# W706.net
KiCad netlist of a schematic drawn in EAGLE
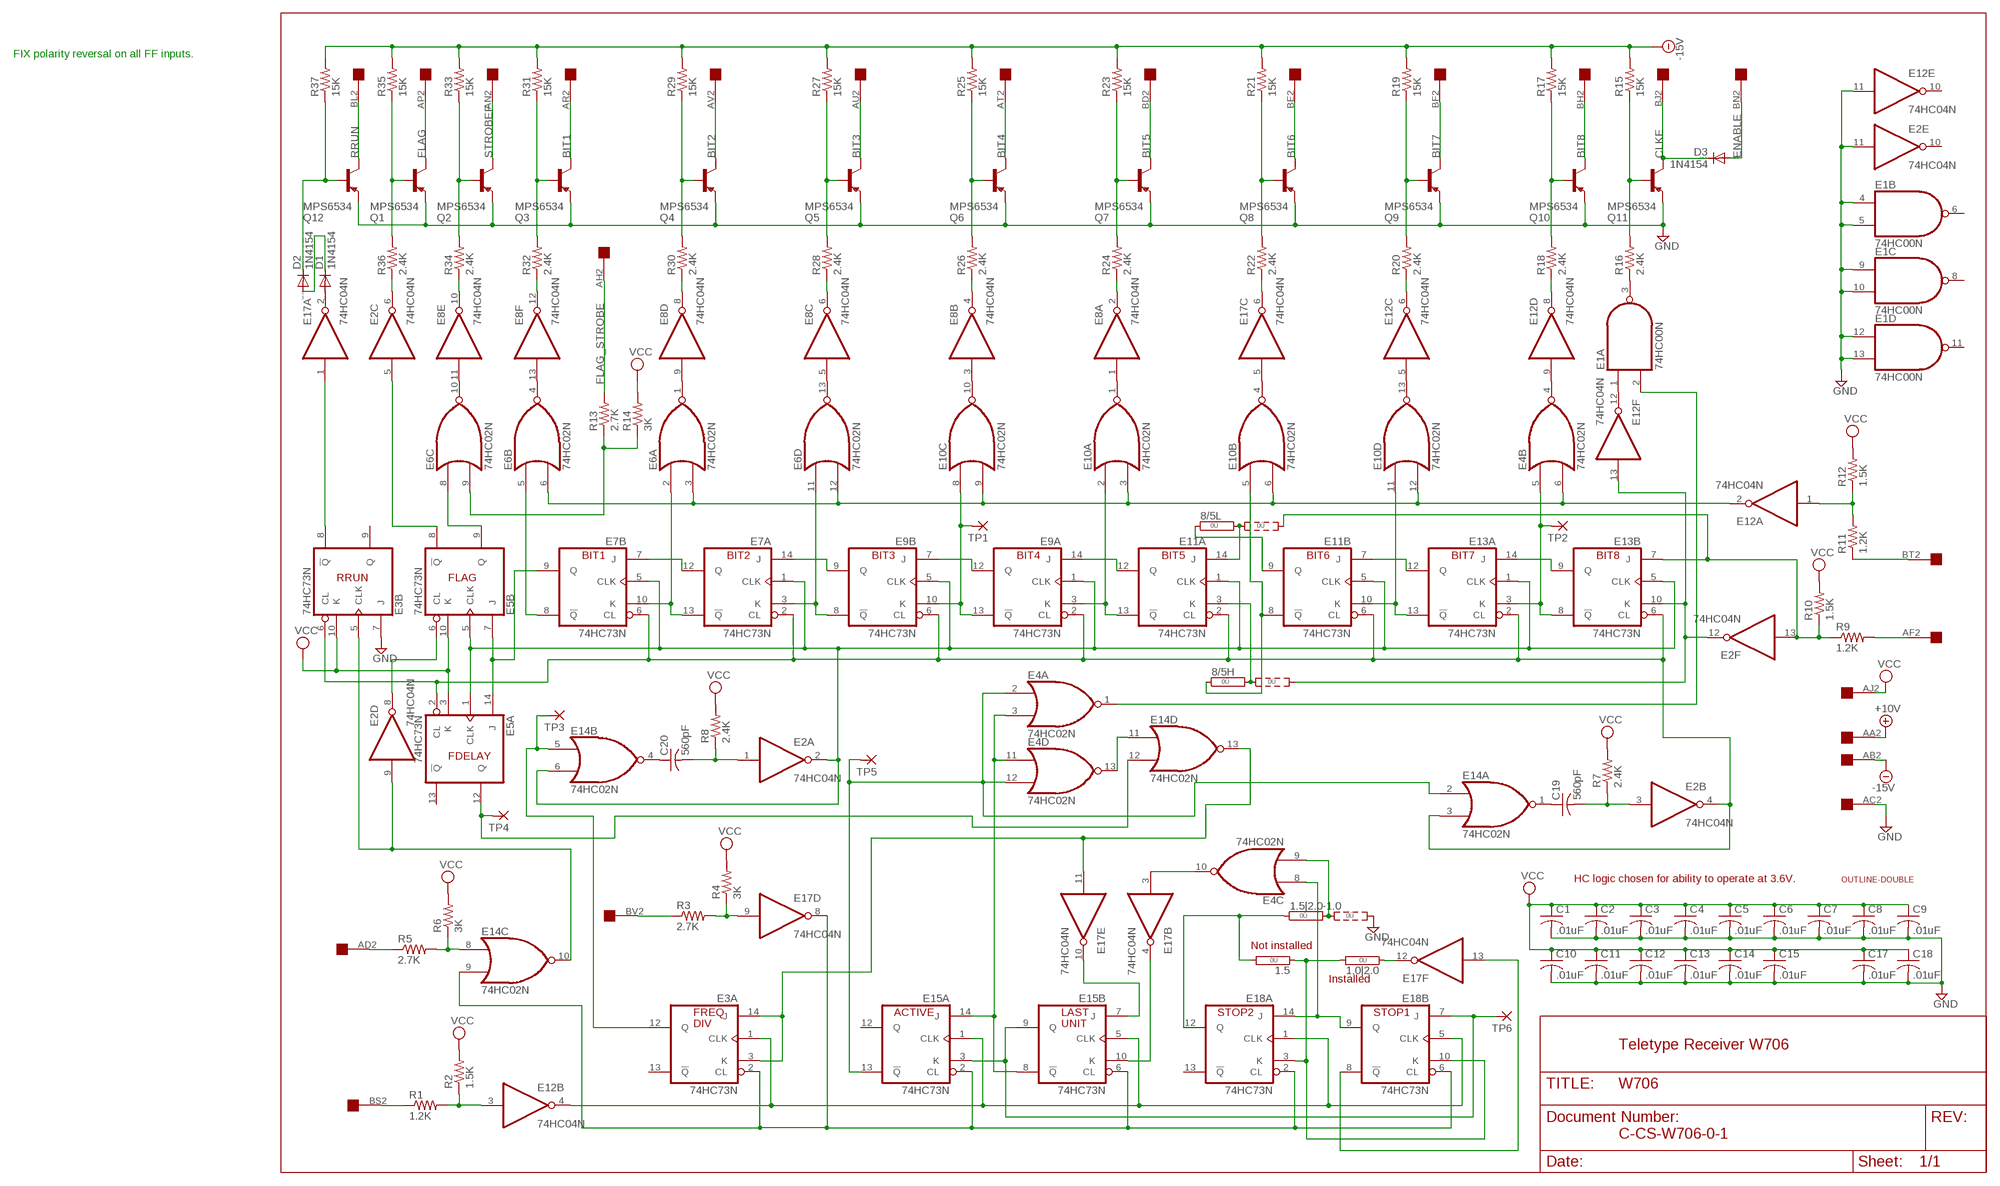
[diagram p0: schematic, sheet 1]

(export (version "E")
  (design (tool "Eeschema 10.0.6"))
  (components
    (comp (ref "1.0|2.0")
      (value "0R")
      (footprint "eagle-import:0R_10")
      (libsource (lib "eagle-import") (part "0R"))
    )
    (comp (ref "1.5")
      (value "0R")
      (footprint "eagle-import:0R_10")
      (libsource (lib "eagle-import") (part "0R"))
    )
    (comp (ref "1.5|2.0-1.0")
      (value "0R2")
      (footprint "eagle-import:0R2_10")
      (libsource (lib "eagle-import") (part "0R2"))
    )
    (comp (ref "8/5H")
      (value "0R2")
      (footprint "eagle-import:0R2_10")
      (libsource (lib "eagle-import") (part "0R2"))
    )
    (comp (ref "8/5L")
      (value "0R2")
      (footprint "eagle-import:0R2_10")
      (libsource (lib "eagle-import") (part "0R2"))
    )
    (comp (ref "C1")
      (value ".01uF")
      (footprint "eagle-import:C050-025X075")
      (libsource (lib "eagle-import") (part "C-US050-025X075"))
    )
    (comp (ref "C2")
      (value ".01uF")
      (footprint "eagle-import:C050-025X075")
      (libsource (lib "eagle-import") (part "C-US050-025X075"))
    )
    (comp (ref "C3")
      (value ".01uF")
      (footprint "eagle-import:C050-025X075")
      (libsource (lib "eagle-import") (part "C-US050-025X075"))
    )
    (comp (ref "C4")
      (value ".01uF")
      (footprint "eagle-import:C050-025X075")
      (libsource (lib "eagle-import") (part "C-US050-025X075"))
    )
    (comp (ref "C5")
      (value ".01uF")
      (footprint "eagle-import:C050-025X075")
      (libsource (lib "eagle-import") (part "C-US050-025X075"))
    )
    (comp (ref "C6")
      (value ".01uF")
      (footprint "eagle-import:C050-025X075")
      (libsource (lib "eagle-import") (part "C-US050-025X075"))
    )
    (comp (ref "C7")
      (value ".01uF")
      (footprint "eagle-import:C050-025X075")
      (libsource (lib "eagle-import") (part "C-US050-025X075"))
    )
    (comp (ref "C8")
      (value ".01uF")
      (footprint "eagle-import:C050-025X075")
      (libsource (lib "eagle-import") (part "C-US050-025X075"))
    )
    (comp (ref "C9")
      (value ".01uF")
      (footprint "eagle-import:C050-025X075")
      (libsource (lib "eagle-import") (part "C-US050-025X075"))
    )
    (comp (ref "C10")
      (value ".01uF")
      (footprint "eagle-import:C050-025X075")
      (libsource (lib "eagle-import") (part "C-US050-025X075"))
    )
    (comp (ref "C11")
      (value ".01uF")
      (footprint "eagle-import:C050-025X075")
      (libsource (lib "eagle-import") (part "C-US050-025X075"))
    )
    (comp (ref "C12")
      (value ".01uF")
      (footprint "eagle-import:C050-025X075")
      (libsource (lib "eagle-import") (part "C-US050-025X075"))
    )
    (comp (ref "C13")
      (value ".01uF")
      (footprint "eagle-import:C050-025X075")
      (libsource (lib "eagle-import") (part "C-US050-025X075"))
    )
    (comp (ref "C14")
      (value ".01uF")
      (footprint "eagle-import:C050-025X075")
      (libsource (lib "eagle-import") (part "C-US050-025X075"))
    )
    (comp (ref "C15")
      (value ".01uF")
      (footprint "eagle-import:C050-025X075")
      (libsource (lib "eagle-import") (part "C-US050-025X075"))
    )
    (comp (ref "C17")
      (value ".01uF")
      (footprint "eagle-import:C050-025X075")
      (libsource (lib "eagle-import") (part "C-US050-025X075"))
    )
    (comp (ref "C18")
      (value ".01uF")
      (footprint "eagle-import:C050-025X075")
      (libsource (lib "eagle-import") (part "C-US050-025X075"))
    )
    (comp (ref "C19")
      (value "560pF")
      (footprint "eagle-import:C050-025X075")
      (libsource (lib "eagle-import") (part "C-US050-025X075"))
    )
    (comp (ref "C20")
      (value "560pF")
      (footprint "eagle-import:C050-025X075")
      (libsource (lib "eagle-import") (part "C-US050-025X075"))
    )
    (comp (ref "D1")
      (value "1N4154")
      (footprint "eagle-import:DO35-10")
      (libsource (lib "eagle-import") (part "1N4148DO35-10"))
    )
    (comp (ref "D2")
      (value "1N4154")
      (footprint "eagle-import:DO35-10")
      (libsource (lib "eagle-import") (part "1N4148DO35-10"))
    )
    (comp (ref "D3")
      (value "1N4154")
      (footprint "eagle-import:DO35-10")
      (libsource (lib "eagle-import") (part "1N4148DO35-10"))
    )
    (comp (ref "E1")
      (value "74HC00N")
      (footprint "eagle-import:DIL14")
      (libsource (lib "eagle-import") (part "7400NLS"))
    )
    (comp (ref "E2")
      (value "74HC04N")
      (footprint "eagle-import:DIL14")
      (libsource (lib "eagle-import") (part "7404NLS"))
    )
    (comp (ref "E3")
      (value "74HC73N")
      (footprint "eagle-import:DIL14")
      (libsource (lib "eagle-import") (part "7473NLS"))
    )
    (comp (ref "E4")
      (value "74HC02N")
      (footprint "eagle-import:DIL14")
      (libsource (lib "eagle-import") (part "7402NLS"))
    )
    (comp (ref "E5")
      (value "74HC73N")
      (footprint "eagle-import:DIL14")
      (libsource (lib "eagle-import") (part "7473NLS"))
    )
    (comp (ref "E6")
      (value "74HC02N")
      (footprint "eagle-import:DIL14")
      (libsource (lib "eagle-import") (part "7402NLS"))
    )
    (comp (ref "E7")
      (value "74HC73N")
      (footprint "eagle-import:DIL14")
      (libsource (lib "eagle-import") (part "7473NLS"))
    )
    (comp (ref "E8")
      (value "74HC04N")
      (footprint "eagle-import:DIL14")
      (libsource (lib "eagle-import") (part "7404NLS"))
    )
    (comp (ref "E9")
      (value "74HC73N")
      (footprint "eagle-import:DIL14")
      (libsource (lib "eagle-import") (part "7473NLS"))
    )
    (comp (ref "E10")
      (value "74HC02N")
      (footprint "eagle-import:DIL14")
      (libsource (lib "eagle-import") (part "7402NLS"))
    )
    (comp (ref "E11")
      (value "74HC73N")
      (footprint "eagle-import:DIL14")
      (libsource (lib "eagle-import") (part "7473NLS"))
    )
    (comp (ref "E12")
      (value "74HC04N")
      (footprint "eagle-import:DIL14")
      (libsource (lib "eagle-import") (part "7404NLS"))
    )
    (comp (ref "E13")
      (value "74HC73N")
      (footprint "eagle-import:DIL14")
      (libsource (lib "eagle-import") (part "7473NLS"))
    )
    (comp (ref "E14")
      (value "74HC02N")
      (footprint "eagle-import:DIL14")
      (libsource (lib "eagle-import") (part "7402NLS"))
    )
    (comp (ref "E15")
      (value "74HC73N")
      (footprint "eagle-import:DIL14")
      (libsource (lib "eagle-import") (part "7473NLS"))
    )
    (comp (ref "E17")
      (value "74HC04N")
      (footprint "eagle-import:DIL14")
      (libsource (lib "eagle-import") (part "7404NLS"))
    )
    (comp (ref "E18")
      (value "74HC73N")
      (footprint "eagle-import:DIL14")
      (libsource (lib "eagle-import") (part "7473NLS"))
    )
    (comp (ref "Q1")
      (value "MPS6534")
      (footprint "eagle-import:TO39")
      (libsource (lib "eagle-import") (part "2N2904"))
    )
    (comp (ref "Q2")
      (value "MPS6534")
      (footprint "eagle-import:TO39")
      (libsource (lib "eagle-import") (part "2N2904"))
    )
    (comp (ref "Q3")
      (value "MPS6534")
      (footprint "eagle-import:TO39")
      (libsource (lib "eagle-import") (part "2N2904"))
    )
    (comp (ref "Q4")
      (value "MPS6534")
      (footprint "eagle-import:TO39")
      (libsource (lib "eagle-import") (part "2N2904"))
    )
    (comp (ref "Q5")
      (value "MPS6534")
      (footprint "eagle-import:TO39")
      (libsource (lib "eagle-import") (part "2N2904"))
    )
    (comp (ref "Q6")
      (value "MPS6534")
      (footprint "eagle-import:TO39")
      (libsource (lib "eagle-import") (part "2N2904"))
    )
    (comp (ref "Q7")
      (value "MPS6534")
      (footprint "eagle-import:TO39")
      (libsource (lib "eagle-import") (part "2N2904"))
    )
    (comp (ref "Q8")
      (value "MPS6534")
      (footprint "eagle-import:TO39")
      (libsource (lib "eagle-import") (part "2N2904"))
    )
    (comp (ref "Q9")
      (value "MPS6534")
      (footprint "eagle-import:TO39")
      (libsource (lib "eagle-import") (part "2N2904"))
    )
    (comp (ref "Q10")
      (value "MPS6534")
      (footprint "eagle-import:TO39")
      (libsource (lib "eagle-import") (part "2N2904"))
    )
    (comp (ref "Q11")
      (value "MPS6534")
      (footprint "eagle-import:TO39")
      (libsource (lib "eagle-import") (part "2N2904"))
    )
    (comp (ref "Q12")
      (value "MPS6534")
      (footprint "eagle-import:TO39")
      (libsource (lib "eagle-import") (part "2N2904"))
    )
    (comp (ref "R1")
      (value "1.2K")
      (footprint "eagle-import:0207_10")
      (libsource (lib "eagle-import") (part "R-US_0207/10"))
    )
    (comp (ref "R2")
      (value "1.5K")
      (footprint "eagle-import:0207_10")
      (libsource (lib "eagle-import") (part "R-US_0207/10"))
    )
    (comp (ref "R3")
      (value "2.7K")
      (footprint "eagle-import:0207_10")
      (libsource (lib "eagle-import") (part "R-US_0207/10"))
    )
    (comp (ref "R4")
      (value "3K")
      (footprint "eagle-import:0207_10")
      (libsource (lib "eagle-import") (part "R-US_0207/10"))
    )
    (comp (ref "R5")
      (value "2.7K")
      (footprint "eagle-import:0207_10")
      (libsource (lib "eagle-import") (part "R-US_0207/10"))
    )
    (comp (ref "R6")
      (value "3K")
      (footprint "eagle-import:0207_10")
      (libsource (lib "eagle-import") (part "R-US_0207/10"))
    )
    (comp (ref "R7")
      (value "2.4K")
      (footprint "eagle-import:0207_10")
      (libsource (lib "eagle-import") (part "R-US_0207/10"))
    )
    (comp (ref "R8")
      (value "2.4K")
      (footprint "eagle-import:0207_10")
      (libsource (lib "eagle-import") (part "R-US_0207/10"))
    )
    (comp (ref "R9")
      (value "1.2K")
      (footprint "eagle-import:0207_10")
      (libsource (lib "eagle-import") (part "R-US_0207/10"))
    )
    (comp (ref "R10")
      (value "1.5K")
      (footprint "eagle-import:0207_10")
      (libsource (lib "eagle-import") (part "R-US_0207/10"))
    )
    (comp (ref "R11")
      (value "1.2K")
      (footprint "eagle-import:0207_10")
      (libsource (lib "eagle-import") (part "R-US_0207/10"))
    )
    (comp (ref "R12")
      (value "1.5K")
      (footprint "eagle-import:0207_10")
      (libsource (lib "eagle-import") (part "R-US_0207/10"))
    )
    (comp (ref "R13")
      (value "2.7K")
      (footprint "eagle-import:0207_10")
      (libsource (lib "eagle-import") (part "R-US_0207/10"))
    )
    (comp (ref "R14")
      (value "3K")
      (footprint "eagle-import:0207_10")
      (libsource (lib "eagle-import") (part "R-US_0207/10"))
    )
    (comp (ref "R15")
      (value "15K")
      (footprint "eagle-import:0207_10")
      (libsource (lib "eagle-import") (part "R-US_0207/10"))
    )
    (comp (ref "R16")
      (value "2.4K")
      (footprint "eagle-import:0207_10")
      (libsource (lib "eagle-import") (part "R-US_0207/10"))
    )
    (comp (ref "R17")
      (value "15K")
      (footprint "eagle-import:0207_10")
      (libsource (lib "eagle-import") (part "R-US_0207/10"))
    )
    (comp (ref "R18")
      (value "2.4K")
      (footprint "eagle-import:0207_10")
      (libsource (lib "eagle-import") (part "R-US_0207/10"))
    )
    (comp (ref "R19")
      (value "15K")
      (footprint "eagle-import:0207_10")
      (libsource (lib "eagle-import") (part "R-US_0207/10"))
    )
    (comp (ref "R20")
      (value "2.4K")
      (footprint "eagle-import:0207_10")
      (libsource (lib "eagle-import") (part "R-US_0207/10"))
    )
    (comp (ref "R21")
      (value "15K")
      (footprint "eagle-import:0207_10")
      (libsource (lib "eagle-import") (part "R-US_0207/10"))
    )
    (comp (ref "R22")
      (value "2.4K")
      (footprint "eagle-import:0207_10")
      (libsource (lib "eagle-import") (part "R-US_0207/10"))
    )
    (comp (ref "R23")
      (value "15K")
      (footprint "eagle-import:0207_10")
      (libsource (lib "eagle-import") (part "R-US_0207/10"))
    )
    (comp (ref "R24")
      (value "2.4K")
      (footprint "eagle-import:0207_10")
      (libsource (lib "eagle-import") (part "R-US_0207/10"))
    )
    (comp (ref "R25")
      (value "15K")
      (footprint "eagle-import:0207_10")
      (libsource (lib "eagle-import") (part "R-US_0207/10"))
    )
    (comp (ref "R26")
      (value "2.4K")
      (footprint "eagle-import:0207_10")
      (libsource (lib "eagle-import") (part "R-US_0207/10"))
    )
    (comp (ref "R27")
      (value "15K")
      (footprint "eagle-import:0207_10")
      (libsource (lib "eagle-import") (part "R-US_0207/10"))
    )
    (comp (ref "R28")
      (value "2.4K")
      (footprint "eagle-import:0207_10")
      (libsource (lib "eagle-import") (part "R-US_0207/10"))
    )
    (comp (ref "R29")
      (value "15K")
      (footprint "eagle-import:0207_10")
      (libsource (lib "eagle-import") (part "R-US_0207/10"))
    )
    (comp (ref "R30")
      (value "2.4K")
      (footprint "eagle-import:0207_10")
      (libsource (lib "eagle-import") (part "R-US_0207/10"))
    )
    (comp (ref "R31")
      (value "15K")
      (footprint "eagle-import:0207_10")
      (libsource (lib "eagle-import") (part "R-US_0207/10"))
    )
    (comp (ref "R32")
      (value "2.4K")
      (footprint "eagle-import:0207_10")
      (libsource (lib "eagle-import") (part "R-US_0207/10"))
    )
    (comp (ref "R33")
      (value "15K")
      (footprint "eagle-import:0207_10")
      (libsource (lib "eagle-import") (part "R-US_0207/10"))
    )
    (comp (ref "R34")
      (value "2.4K")
      (footprint "eagle-import:0207_10")
      (libsource (lib "eagle-import") (part "R-US_0207/10"))
    )
    (comp (ref "R35")
      (value "15K")
      (footprint "eagle-import:0207_10")
      (libsource (lib "eagle-import") (part "R-US_0207/10"))
    )
    (comp (ref "R36")
      (value "2.4K")
      (footprint "eagle-import:0207_10")
      (libsource (lib "eagle-import") (part "R-US_0207/10"))
    )
    (comp (ref "R37")
      (value "15K")
      (footprint "eagle-import:0207_10")
      (libsource (lib "eagle-import") (part "R-US_0207/10"))
    )
    (comp (ref "TP1")
      (value "3,17/1,3")
      (footprint "eagle-import:3,17_1,3")
      (libsource (lib "eagle-import") (part "3,17/1,3"))
    )
    (comp (ref "TP2")
      (value "3,17/1,3")
      (footprint "eagle-import:3,17_1,3")
      (libsource (lib "eagle-import") (part "3,17/1,3"))
    )
    (comp (ref "TP3")
      (value "3,17/1,3")
      (footprint "eagle-import:3,17_1,3")
      (libsource (lib "eagle-import") (part "3,17/1,3"))
    )
    (comp (ref "TP4")
      (value "3,17/1,3")
      (footprint "eagle-import:3,17_1,3")
      (libsource (lib "eagle-import") (part "3,17/1,3"))
    )
    (comp (ref "TP5")
      (value "3,17/1,3")
      (footprint "eagle-import:3,17_1,3")
      (libsource (lib "eagle-import") (part "3,17/1,3"))
    )
    (comp (ref "TP6")
      (value "3,17/1,3")
      (footprint "eagle-import:3,17_1,3")
      (libsource (lib "eagle-import") (part "3,17/1,3"))
    )
    (comp (ref "U$1")
      (value "OUTLINE-DOUBLE")
      (footprint "eagle-import:DOUBLE")
      (libsource (lib "eagle-import") (part "OUTLINE-DOUBLE"))
    )
    (comp (ref "U$2")
      (value "DOUBLE")
      (footprint "eagle-import:EDGE-CON4")
      (libsource (lib "eagle-import") (part "DOUBLE"))
    )
  )
  (nets
    (net (code "1") (name "+10V") (class "Default")
      (node (ref "U$2") (pin "AA2") (pinfunction "1_AA2") (pintype "bidirectional"))
    )
    (net (code "2") (name "-15V") (class "Default")
      (node (ref "R15") (pin "2") (pinfunction "2_2") (pintype "passive"))
      (node (ref "R17") (pin "2") (pinfunction "2_2") (pintype "passive"))
      (node (ref "R19") (pin "2") (pinfunction "2_2") (pintype "passive"))
      (node (ref "R21") (pin "2") (pinfunction "2_2") (pintype "passive"))
      (node (ref "R23") (pin "2") (pinfunction "2_2") (pintype "passive"))
      (node (ref "R25") (pin "2") (pinfunction "2_2") (pintype "passive"))
      (node (ref "R27") (pin "2") (pinfunction "2_2") (pintype "passive"))
      (node (ref "R29") (pin "2") (pinfunction "2_2") (pintype "passive"))
      (node (ref "R31") (pin "2") (pinfunction "2_2") (pintype "passive"))
      (node (ref "R33") (pin "2") (pinfunction "2_2") (pintype "passive"))
      (node (ref "R35") (pin "2") (pinfunction "2_2") (pintype "passive"))
      (node (ref "R37") (pin "2") (pinfunction "2_2") (pintype "passive"))
      (node (ref "U$2") (pin "AB2") (pinfunction "1_AB2") (pintype "bidirectional"))
    )
    (net (code "3") (name "/BIT1") (class "Default")
      (node (ref "Q3") (pin "3") (pinfunction "C_3") (pintype "passive"))
      (node (ref "U$2") (pin "AR2") (pinfunction "1_AR2") (pintype "bidirectional"))
    )
    (net (code "4") (name "/BIT2") (class "Default")
      (node (ref "Q4") (pin "3") (pinfunction "C_3") (pintype "passive"))
      (node (ref "U$2") (pin "AV2") (pinfunction "1_AV2") (pintype "bidirectional"))
    )
    (net (code "5") (name "/BIT3") (class "Default")
      (node (ref "Q5") (pin "3") (pinfunction "C_3") (pintype "passive"))
      (node (ref "U$2") (pin "AU2") (pinfunction "1_AU2") (pintype "bidirectional"))
    )
    (net (code "6") (name "/BIT4") (class "Default")
      (node (ref "Q6") (pin "3") (pinfunction "C_3") (pintype "passive"))
      (node (ref "U$2") (pin "AT2") (pinfunction "1_AT2") (pintype "bidirectional"))
    )
    (net (code "7") (name "/BIT5") (class "Default")
      (node (ref "Q7") (pin "3") (pinfunction "C_3") (pintype "passive"))
      (node (ref "U$2") (pin "BD2") (pinfunction "1_BD2") (pintype "bidirectional"))
    )
    (net (code "8") (name "/BIT6") (class "Default")
      (node (ref "Q8") (pin "3") (pinfunction "C_3") (pintype "passive"))
      (node (ref "U$2") (pin "BE2") (pinfunction "1_BE2") (pintype "bidirectional"))
    )
    (net (code "9") (name "/BIT7") (class "Default")
      (node (ref "Q9") (pin "3") (pinfunction "C_3") (pintype "passive"))
      (node (ref "U$2") (pin "BF2") (pinfunction "1_BF2") (pintype "bidirectional"))
    )
    (net (code "10") (name "/BIT8") (class "Default")
      (node (ref "Q10") (pin "3") (pinfunction "C_3") (pintype "passive"))
      (node (ref "U$2") (pin "BH2") (pinfunction "1_BH2") (pintype "bidirectional"))
    )
    (net (code "11") (name "/CLKE") (class "Default")
      (node (ref "D3") (pin "C") (pinfunction "C_C") (pintype "passive"))
      (node (ref "Q11") (pin "3") (pinfunction "C_3") (pintype "passive"))
      (node (ref "U$2") (pin "BJ2") (pinfunction "1_BJ2") (pintype "bidirectional"))
    )
    (net (code "12") (name "/ENABLE") (class "Default")
      (node (ref "D3") (pin "A") (pinfunction "A_A") (pintype "passive"))
      (node (ref "U$2") (pin "BN2") (pinfunction "1_BN2") (pintype "bidirectional"))
    )
    (net (code "13") (name "/FLAG") (class "Default")
      (node (ref "Q1") (pin "3") (pinfunction "C_3") (pintype "passive"))
      (node (ref "U$2") (pin "AP2") (pinfunction "1_AP2") (pintype "bidirectional"))
    )
    (net (code "14") (name "/FLAG_STROBE") (class "Default")
      (node (ref "R13") (pin "2") (pinfunction "2_2") (pintype "passive"))
      (node (ref "U$2") (pin "AH2") (pinfunction "1_AH2") (pintype "bidirectional"))
    )
    (net (code "15") (name "/RRUN") (class "Default")
      (node (ref "Q12") (pin "3") (pinfunction "C_3") (pintype "passive"))
      (node (ref "U$2") (pin "BL2") (pinfunction "1_BL2") (pintype "bidirectional"))
    )
    (net (code "16") (name "/STROBEF") (class "Default")
      (node (ref "Q2") (pin "3") (pinfunction "C_3") (pintype "passive"))
      (node (ref "U$2") (pin "AN2") (pinfunction "1_AN2") (pintype "bidirectional"))
    )
    (net (code "17") (name "GND") (class "Default")
      (node (ref "1.5|2.0-1.0") (pin "3") (pinfunction "3_3") (pintype "passive"))
      (node (ref "C1") (pin "2") (pinfunction "2_2") (pintype "passive"))
      (node (ref "C10") (pin "2") (pinfunction "2_2") (pintype "passive"))
      (node (ref "C11") (pin "2") (pinfunction "2_2") (pintype "passive"))
      (node (ref "C12") (pin "2") (pinfunction "2_2") (pintype "passive"))
      (node (ref "C13") (pin "2") (pinfunction "2_2") (pintype "passive"))
      (node (ref "C14") (pin "2") (pinfunction "2_2") (pintype "passive"))
      (node (ref "C15") (pin "2") (pinfunction "2_2") (pintype "passive"))
      (node (ref "C17") (pin "2") (pinfunction "2_2") (pintype "passive"))
      (node (ref "C18") (pin "2") (pinfunction "2_2") (pintype "passive"))
      (node (ref "C2") (pin "2") (pinfunction "2_2") (pintype "passive"))
      (node (ref "C3") (pin "2") (pinfunction "2_2") (pintype "passive"))
      (node (ref "C4") (pin "2") (pinfunction "2_2") (pintype "passive"))
      (node (ref "C5") (pin "2") (pinfunction "2_2") (pintype "passive"))
      (node (ref "C6") (pin "2") (pinfunction "2_2") (pintype "passive"))
      (node (ref "C7") (pin "2") (pinfunction "2_2") (pintype "passive"))
      (node (ref "C8") (pin "2") (pinfunction "2_2") (pintype "passive"))
      (node (ref "C9") (pin "2") (pinfunction "2_2") (pintype "passive"))
      (node (ref "E1") (pin "10") (pinfunction "I1_10") (pintype "input"))
      (node (ref "E1") (pin "12") (pinfunction "I0_12") (pintype "input"))
      (node (ref "E1") (pin "13") (pinfunction "I1_13") (pintype "input"))
      (node (ref "E1") (pin "4") (pinfunction "I0_4") (pintype "input"))
      (node (ref "E1") (pin "5") (pinfunction "I1_5") (pintype "input"))
      (node (ref "E1") (pin "9") (pinfunction "I0_9") (pintype "input"))
      (node (ref "E12") (pin "11") (pinfunction "I_11") (pintype "input"))
      (node (ref "E2") (pin "11") (pinfunction "I_11") (pintype "input"))
      (node (ref "E3") (pin "7") (pinfunction "J_7") (pintype "input"))
      (node (ref "Q1") (pin "1") (pinfunction "E_1") (pintype "passive"))
      (node (ref "Q10") (pin "1") (pinfunction "E_1") (pintype "passive"))
      (node (ref "Q11") (pin "1") (pinfunction "E_1") (pintype "passive"))
      (node (ref "Q12") (pin "1") (pinfunction "E_1") (pintype "passive"))
      (node (ref "Q2") (pin "1") (pinfunction "E_1") (pintype "passive"))
      (node (ref "Q3") (pin "1") (pinfunction "E_1") (pintype "passive"))
      (node (ref "Q4") (pin "1") (pinfunction "E_1") (pintype "passive"))
      (node (ref "Q5") (pin "1") (pinfunction "E_1") (pintype "passive"))
      (node (ref "Q6") (pin "1") (pinfunction "E_1") (pintype "passive"))
      (node (ref "Q7") (pin "1") (pinfunction "E_1") (pintype "passive"))
      (node (ref "Q8") (pin "1") (pinfunction "E_1") (pintype "passive"))
      (node (ref "Q9") (pin "1") (pinfunction "E_1") (pintype "passive"))
      (node (ref "U$2") (pin "AC2") (pinfunction "1_AC2") (pintype "bidirectional"))
    )
    (net (code "18") (name "Net-(D1-PadC)") (class "Default")
      (node (ref "D1") (pin "C") (pinfunction "C_C") (pintype "passive"))
      (node (ref "D2") (pin "A") (pinfunction "A_A") (pintype "passive"))
    )
    (net (code "19") (name "Net-(E1A-I1)") (class "Default")
      (node (ref "E1") (pin "2") (pinfunction "I1_2") (pintype "input"))
      (node (ref "E4") (pin "1") (pinfunction "O_1") (pintype "output"))
    )
    (net (code "20") (name "Net-(E1A-O)") (class "Default")
      (node (ref "E1") (pin "3") (pinfunction "O_3") (pintype "output"))
      (node (ref "R16") (pin "1") (pinfunction "1_1") (pintype "passive"))
    )
    (net (code "21") (name "Net-(E2A-I)") (class "Default")
      (node (ref "C20") (pin "2") (pinfunction "2_2") (pintype "passive"))
      (node (ref "E2") (pin "1") (pinfunction "I_1") (pintype "input"))
      (node (ref "R8") (pin "1") (pinfunction "1_1") (pintype "passive"))
    )
    (net (code "22") (name "Net-(E2B-I)") (class "Default")
      (node (ref "C19") (pin "2") (pinfunction "2_2") (pintype "passive"))
      (node (ref "E2") (pin "3") (pinfunction "I_3") (pintype "input"))
      (node (ref "R7") (pin "1") (pinfunction "1_1") (pintype "passive"))
    )
    (net (code "23") (name "Net-(E2C-I)") (class "Default")
      (node (ref "E2") (pin "5") (pinfunction "I_5") (pintype "input"))
      (node (ref "E5") (pin "8") (pinfunction "~{Q}_8") (pintype "output"))
    )
    (net (code "24") (name "Net-(E2C-O)") (class "Default")
      (node (ref "E2") (pin "6") (pinfunction "O_6") (pintype "output"))
      (node (ref "R36") (pin "1") (pinfunction "1_1") (pintype "passive"))
    )
    (net (code "25") (name "Net-(E2D-O)") (class "Default")
      (node (ref "E2") (pin "8") (pinfunction "O_8") (pintype "output"))
      (node (ref "E5") (pin "6") (pinfunction "CL_6") (pintype "input"))
    )
    (net (code "26") (name "Net-(E4C-I1)") (class "Default")
      (node (ref "1.5|2.0-1.0") (pin "2") (pinfunction "2_2") (pintype "passive"))
      (node (ref "E4") (pin "9") (pinfunction "I1_9") (pintype "input"))
    )
    (net (code "27") (name "Net-(E5A-J)") (class "Default")
      (node (ref "E5") (pin "14") (pinfunction "J_14") (pintype "input"))
      (node (ref "E5") (pin "7") (pinfunction "J_7") (pintype "input"))
      (node (ref "E7") (pin "9") (pinfunction "Q_9") (pintype "output"))
    )
    (net (code "28") (name "Net-(E5B-Q)") (class "Default")
      (node (ref "E5") (pin "9") (pinfunction "Q_9") (pintype "output"))
      (node (ref "E6") (pin "8") (pinfunction "I0_8") (pintype "input"))
    )
    (net (code "29") (name "Net-(E6A-I0)") (class "Default")
      (node (ref "E6") (pin "2") (pinfunction "I0_2") (pintype "input"))
      (node (ref "E7") (pin "10") (pinfunction "K_10") (pintype "input"))
      (node (ref "E7") (pin "13") (pinfunction "~{Q}_13") (pintype "output"))
    )
    (net (code "30") (name "Net-(E6A-O)") (class "Default")
      (node (ref "E6") (pin "1") (pinfunction "O_1") (pintype "output"))
      (node (ref "E8") (pin "9") (pinfunction "I_9") (pintype "input"))
    )
    (net (code "31") (name "Net-(E6B-I0)") (class "Default")
      (node (ref "E6") (pin "5") (pinfunction "I0_5") (pintype "input"))
      (node (ref "E7") (pin "8") (pinfunction "~{Q}_8") (pintype "output"))
    )
    (net (code "32") (name "Net-(E6B-O)") (class "Default")
      (node (ref "E6") (pin "4") (pinfunction "O_4") (pintype "output"))
      (node (ref "E8") (pin "13") (pinfunction "I_13") (pintype "input"))
    )
    (net (code "33") (name "Net-(E6C-I1)") (class "Default")
      (node (ref "E6") (pin "9") (pinfunction "I1_9") (pintype "input"))
      (node (ref "R13") (pin "1") (pinfunction "1_1") (pintype "passive"))
      (node (ref "R14") (pin "1") (pinfunction "1_1") (pintype "passive"))
    )
    (net (code "34") (name "Net-(E6C-O)") (class "Default")
      (node (ref "E6") (pin "10") (pinfunction "O_10") (pintype "output"))
      (node (ref "E8") (pin "11") (pinfunction "I_11") (pintype "input"))
    )
    (net (code "35") (name "Net-(E6D-I0)") (class "Default")
      (node (ref "E6") (pin "11") (pinfunction "I0_11") (pintype "input"))
      (node (ref "E7") (pin "3") (pinfunction "K_3") (pintype "input"))
      (node (ref "E9") (pin "8") (pinfunction "~{Q}_8") (pintype "output"))
    )
    (net (code "36") (name "Net-(E6D-O)") (class "Default")
      (node (ref "E6") (pin "13") (pinfunction "O_13") (pintype "output"))
      (node (ref "E8") (pin "5") (pinfunction "I_5") (pintype "input"))
    )
    (net (code "37") (name "Net-(E7A-J)") (class "Default")
      (node (ref "E7") (pin "14") (pinfunction "J_14") (pintype "input"))
      (node (ref "E9") (pin "9") (pinfunction "Q_9") (pintype "output"))
    )
    (net (code "38") (name "Net-(E7A-Q)") (class "Default")
      (node (ref "E7") (pin "12") (pinfunction "Q_12") (pintype "output"))
      (node (ref "E7") (pin "7") (pinfunction "J_7") (pintype "input"))
    )
    (net (code "39") (name "Net-(E8A-O)") (class "Default")
      (node (ref "E8") (pin "2") (pinfunction "O_2") (pintype "output"))
      (node (ref "R24") (pin "1") (pinfunction "1_1") (pintype "passive"))
    )
    (net (code "40") (name "Net-(E8B-O)") (class "Default")
      (node (ref "E8") (pin "4") (pinfunction "O_4") (pintype "output"))
      (node (ref "R26") (pin "1") (pinfunction "1_1") (pintype "passive"))
    )
    (net (code "41") (name "Net-(E8C-O)") (class "Default")
      (node (ref "E8") (pin "6") (pinfunction "O_6") (pintype "output"))
      (node (ref "R28") (pin "1") (pinfunction "1_1") (pintype "passive"))
    )
    (net (code "42") (name "Net-(E8D-O)") (class "Default")
      (node (ref "E8") (pin "8") (pinfunction "O_8") (pintype "output"))
      (node (ref "R30") (pin "1") (pinfunction "1_1") (pintype "passive"))
    )
    (net (code "43") (name "Net-(E8E-O)") (class "Default")
      (node (ref "E8") (pin "10") (pinfunction "O_10") (pintype "output"))
      (node (ref "R34") (pin "1") (pinfunction "1_1") (pintype "passive"))
    )
    (net (code "44") (name "Net-(E8F-O)") (class "Default")
      (node (ref "E8") (pin "12") (pinfunction "O_12") (pintype "output"))
      (node (ref "R32") (pin "1") (pinfunction "1_1") (pintype "passive"))
    )
    (net (code "45") (name "Net-(E9A-Q)") (class "Default")
      (node (ref "E9") (pin "12") (pinfunction "Q_12") (pintype "output"))
      (node (ref "E9") (pin "7") (pinfunction "J_7") (pintype "input"))
    )
    (net (code "46") (name "Net-(E10A-I0)") (class "Default")
      (node (ref "E10") (pin "2") (pinfunction "I0_2") (pintype "input"))
      (node (ref "E11") (pin "13") (pinfunction "~{Q}_13") (pintype "output"))
      (node (ref "E9") (pin "3") (pinfunction "K_3") (pintype "input"))
    )
    (net (code "47") (name "Net-(E10A-I1)") (class "Default")
      (node (ref "E10") (pin "12") (pinfunction "I1_12") (pintype "input"))
      (node (ref "E10") (pin "3") (pinfunction "I1_3") (pintype "input"))
      (node (ref "E10") (pin "6") (pinfunction "I1_6") (pintype "input"))
      (node (ref "E10") (pin "9") (pinfunction "I1_9") (pintype "input"))
      (node (ref "E12") (pin "2") (pinfunction "O_2") (pintype "output"))
      (node (ref "E4") (pin "6") (pinfunction "I1_6") (pintype "input"))
      (node (ref "E6") (pin "12") (pinfunction "I1_12") (pintype "input"))
      (node (ref "E6") (pin "3") (pinfunction "I1_3") (pintype "input"))
      (node (ref "E6") (pin "6") (pinfunction "I1_6") (pintype "input"))
    )
    (net (code "48") (name "Net-(E10A-O)") (class "Default")
      (node (ref "E10") (pin "1") (pinfunction "O_1") (pintype "output"))
      (node (ref "E8") (pin "1") (pinfunction "I_1") (pintype "input"))
    )
    (net (code "49") (name "Net-(E10B-I0)") (class "Default")
      (node (ref "8/5H") (pin "1") (pinfunction "1_1") (pintype "passive"))
      (node (ref "E10") (pin "5") (pinfunction "I0_5") (pintype "input"))
      (node (ref "E11") (pin "8") (pinfunction "~{Q}_8") (pintype "output"))
    )
    (net (code "50") (name "Net-(E10B-O)") (class "Default")
      (node (ref "E10") (pin "4") (pinfunction "O_4") (pintype "output"))
      (node (ref "E17") (pin "5") (pinfunction "I_5") (pintype "input"))
    )
    (net (code "51") (name "Net-(E10C-I0)") (class "Default")
      (node (ref "E10") (pin "8") (pinfunction "I0_8") (pintype "input"))
      (node (ref "E9") (pin "10") (pinfunction "K_10") (pintype "input"))
      (node (ref "E9") (pin "13") (pinfunction "~{Q}_13") (pintype "output"))
      (node (ref "TP1") (pin "1") (pinfunction "P_1") (pintype "passive"))
    )
    (net (code "52") (name "Net-(E10C-O)") (class "Default")
      (node (ref "E10") (pin "10") (pinfunction "O_10") (pintype "output"))
      (node (ref "E8") (pin "3") (pinfunction "I_3") (pintype "input"))
    )
    (net (code "53") (name "Net-(E10D-I0)") (class "Default")
      (node (ref "E10") (pin "11") (pinfunction "I0_11") (pintype "input"))
      (node (ref "E11") (pin "10") (pinfunction "K_10") (pintype "input"))
      (node (ref "E13") (pin "13") (pinfunction "~{Q}_13") (pintype "output"))
    )
    (net (code "54") (name "Net-(E10D-O)") (class "Default")
      (node (ref "E10") (pin "13") (pinfunction "O_13") (pintype "output"))
      (node (ref "E12") (pin "5") (pinfunction "I_5") (pintype "input"))
    )
    (net (code "55") (name "Net-(E11A-CL)") (class "Default")
      (node (ref "E11") (pin "2") (pinfunction "CL_2") (pintype "input"))
      (node (ref "E11") (pin "6") (pinfunction "CL_6") (pintype "input"))
      (node (ref "E13") (pin "2") (pinfunction "CL_2") (pintype "input"))
      (node (ref "E13") (pin "6") (pinfunction "CL_6") (pintype "input"))
      (node (ref "E14") (pin "3") (pinfunction "I1_3") (pintype "input"))
      (node (ref "E2") (pin "4") (pinfunction "O_4") (pintype "output"))
      (node (ref "E3") (pin "6") (pinfunction "CL_6") (pintype "input"))
      (node (ref "E5") (pin "2") (pinfunction "CL_2") (pintype "input"))
      (node (ref "E7") (pin "2") (pinfunction "CL_2") (pintype "input"))
      (node (ref "E7") (pin "6") (pinfunction "CL_6") (pintype "input"))
      (node (ref "E9") (pin "2") (pinfunction "CL_2") (pintype "input"))
      (node (ref "E9") (pin "6") (pinfunction "CL_6") (pintype "input"))
    )
    (net (code "56") (name "Net-(E11A-CLK)") (class "Default")
      (node (ref "E11") (pin "1") (pinfunction "CLK_1") (pintype "input"))
      (node (ref "E11") (pin "5") (pinfunction "CLK_5") (pintype "input"))
      (node (ref "E13") (pin "1") (pinfunction "CLK_1") (pintype "input"))
      (node (ref "E13") (pin "5") (pinfunction "CLK_5") (pintype "input"))
      (node (ref "E14") (pin "6") (pinfunction "I1_6") (pintype "input"))
      (node (ref "E2") (pin "2") (pinfunction "O_2") (pintype "output"))
      (node (ref "E5") (pin "1") (pinfunction "CLK_1") (pintype "input"))
      (node (ref "E5") (pin "5") (pinfunction "CLK_5") (pintype "input"))
      (node (ref "E7") (pin "1") (pinfunction "CLK_1") (pintype "input"))
      (node (ref "E7") (pin "5") (pinfunction "CLK_5") (pintype "input"))
      (node (ref "E9") (pin "1") (pinfunction "CLK_1") (pintype "input"))
      (node (ref "E9") (pin "5") (pinfunction "CLK_5") (pintype "input"))
    )
    (net (code "57") (name "Net-(E11A-J)") (class "Default")
      (node (ref "8/5L") (pin "2") (pinfunction "2_2") (pintype "passive"))
      (node (ref "E11") (pin "14") (pinfunction "J_14") (pintype "input"))
    )
    (net (code "58") (name "Net-(E11A-K)") (class "Default")
      (node (ref "8/5H") (pin "2") (pinfunction "2_2") (pintype "passive"))
      (node (ref "E11") (pin "3") (pinfunction "K_3") (pintype "input"))
    )
    (net (code "59") (name "Net-(E11A-Q)") (class "Default")
      (node (ref "E11") (pin "12") (pinfunction "Q_12") (pintype "output"))
      (node (ref "E9") (pin "14") (pinfunction "J_14") (pintype "input"))
    )
    (net (code "60") (name "Net-(E11B-J)") (class "Default")
      (node (ref "E11") (pin "7") (pinfunction "J_7") (pintype "input"))
      (node (ref "E13") (pin "12") (pinfunction "Q_12") (pintype "output"))
    )
    (net (code "61") (name "Net-(E11B-Q)") (class "Default")
      (node (ref "8/5L") (pin "1") (pinfunction "1_1") (pintype "passive"))
      (node (ref "E11") (pin "9") (pinfunction "Q_9") (pintype "output"))
    )
    (net (code "62") (name "Net-(E12A-I)") (class "Default")
      (node (ref "E12") (pin "1") (pinfunction "I_1") (pintype "input"))
      (node (ref "R11") (pin "2") (pinfunction "2_2") (pintype "passive"))
      (node (ref "R12") (pin "1") (pinfunction "1_1") (pintype "passive"))
    )
    (net (code "63") (name "Net-(E12B-I)") (class "Default")
      (node (ref "E12") (pin "3") (pinfunction "I_3") (pintype "input"))
      (node (ref "R1") (pin "2") (pinfunction "2_2") (pintype "passive"))
      (node (ref "R2") (pin "1") (pinfunction "1_1") (pintype "passive"))
    )
    (net (code "64") (name "Net-(E12B-O)") (class "Default")
      (node (ref "E12") (pin "4") (pinfunction "O_4") (pintype "output"))
      (node (ref "E15") (pin "1") (pinfunction "CLK_1") (pintype "input"))
      (node (ref "E15") (pin "5") (pinfunction "CLK_5") (pintype "input"))
      (node (ref "E18") (pin "1") (pinfunction "CLK_1") (pintype "input"))
      (node (ref "E18") (pin "5") (pinfunction "CLK_5") (pintype "input"))
      (node (ref "E3") (pin "1") (pinfunction "CLK_1") (pintype "input"))
    )
    (net (code "65") (name "Net-(E12C-O)") (class "Default")
      (node (ref "E12") (pin "6") (pinfunction "O_6") (pintype "output"))
      (node (ref "R20") (pin "1") (pinfunction "1_1") (pintype "passive"))
    )
    (net (code "66") (name "Net-(E12D-I)") (class "Default")
      (node (ref "E12") (pin "9") (pinfunction "I_9") (pintype "input"))
      (node (ref "E4") (pin "4") (pinfunction "O_4") (pintype "output"))
    )
    (net (code "67") (name "Net-(E12D-O)") (class "Default")
      (node (ref "E12") (pin "8") (pinfunction "O_8") (pintype "output"))
      (node (ref "R18") (pin "1") (pinfunction "1_1") (pintype "passive"))
    )
    (net (code "68") (name "Net-(E12F-I)") (class "Default")
      (node (ref "8/5H") (pin "3") (pinfunction "3_3") (pintype "passive"))
      (node (ref "E12") (pin "13") (pinfunction "I_13") (pintype "input"))
      (node (ref "E13") (pin "10") (pinfunction "K_10") (pintype "input"))
      (node (ref "E2") (pin "12") (pinfunction "O_12") (pintype "output"))
    )
    (net (code "69") (name "Net-(E12F-O)") (class "Default")
      (node (ref "E1") (pin "1") (pinfunction "I0_1") (pintype "input"))
      (node (ref "E12") (pin "12") (pinfunction "O_12") (pintype "output"))
    )
    (net (code "70") (name "Net-(E13A-J)") (class "Default")
      (node (ref "E13") (pin "14") (pinfunction "J_14") (pintype "input"))
      (node (ref "E13") (pin "9") (pinfunction "Q_9") (pintype "output"))
    )
    (net (code "71") (name "Net-(E13A-K)") (class "Default")
      (node (ref "E13") (pin "3") (pinfunction "K_3") (pintype "input"))
      (node (ref "E13") (pin "8") (pinfunction "~{Q}_8") (pintype "output"))
      (node (ref "E4") (pin "5") (pinfunction "I0_5") (pintype "input"))
      (node (ref "TP2") (pin "1") (pinfunction "P_1") (pintype "passive"))
    )
    (net (code "72") (name "Net-(E13B-J)") (class "Default")
      (node (ref "8/5L") (pin "3") (pinfunction "3_3") (pintype "passive"))
      (node (ref "E13") (pin "7") (pinfunction "J_7") (pintype "input"))
      (node (ref "E2") (pin "13") (pinfunction "I_13") (pintype "input"))
      (node (ref "R10") (pin "1") (pinfunction "1_1") (pintype "passive"))
      (node (ref "R9") (pin "1") (pinfunction "1_1") (pintype "passive"))
    )
    (net (code "73") (name "Net-(E14A-I0)") (class "Default")
      (node (ref "E14") (pin "2") (pinfunction "I0_2") (pintype "input"))
      (node (ref "E15") (pin "13") (pinfunction "~{Q}_13") (pintype "output"))
      (node (ref "E4") (pin "12") (pinfunction "I1_12") (pintype "input"))
      (node (ref "E4") (pin "2") (pinfunction "I0_2") (pintype "input"))
      (node (ref "TP5") (pin "1") (pinfunction "P_1") (pintype "passive"))
    )
    (net (code "74") (name "Net-(E14A-O)") (class "Default")
      (node (ref "C19") (pin "1") (pinfunction "1_1") (pintype "passive"))
      (node (ref "E14") (pin "1") (pinfunction "O_1") (pintype "output"))
    )
    (net (code "75") (name "Net-(E14B-I0)") (class "Default")
      (node (ref "E14") (pin "5") (pinfunction "I0_5") (pintype "input"))
      (node (ref "E3") (pin "12") (pinfunction "Q_12") (pintype "output"))
      (node (ref "TP3") (pin "1") (pinfunction "P_1") (pintype "passive"))
    )
    (net (code "76") (name "Net-(E14B-O)") (class "Default")
      (node (ref "C20") (pin "1") (pinfunction "1_1") (pintype "passive"))
      (node (ref "E14") (pin "4") (pinfunction "O_4") (pintype "output"))
    )
    (net (code "77") (name "Net-(E14C-I0)") (class "Default")
      (node (ref "E14") (pin "8") (pinfunction "I0_8") (pintype "input"))
      (node (ref "R5") (pin "2") (pinfunction "2_2") (pintype "passive"))
      (node (ref "R6") (pin "1") (pinfunction "1_1") (pintype "passive"))
    )
    (net (code "78") (name "Net-(E14C-I1)") (class "Default")
      (node (ref "E14") (pin "9") (pinfunction "I1_9") (pintype "input"))
      (node (ref "E15") (pin "2") (pinfunction "CL_2") (pintype "input"))
      (node (ref "E15") (pin "6") (pinfunction "CL_6") (pintype "input"))
      (node (ref "E17") (pin "8") (pinfunction "O_8") (pintype "output"))
      (node (ref "E18") (pin "2") (pinfunction "CL_2") (pintype "input"))
      (node (ref "E18") (pin "6") (pinfunction "CL_6") (pintype "input"))
      (node (ref "E3") (pin "2") (pinfunction "CL_2") (pintype "input"))
    )
    (net (code "79") (name "Net-(E14C-O)") (class "Default")
      (node (ref "E14") (pin "10") (pinfunction "O_10") (pintype "output"))
      (node (ref "E2") (pin "9") (pinfunction "I_9") (pintype "input"))
      (node (ref "E3") (pin "5") (pinfunction "CLK_5") (pintype "input"))
    )
    (net (code "80") (name "Net-(E14D-I0)") (class "Default")
      (node (ref "E14") (pin "11") (pinfunction "I0_11") (pintype "input"))
      (node (ref "E4") (pin "13") (pinfunction "O_13") (pintype "output"))
    )
    (net (code "81") (name "Net-(E14D-I1)") (class "Default")
      (node (ref "E14") (pin "12") (pinfunction "I1_12") (pintype "input"))
      (node (ref "E5") (pin "12") (pinfunction "Q_12") (pintype "output"))
      (node (ref "TP4") (pin "1") (pinfunction "P_1") (pintype "passive"))
    )
    (net (code "82") (name "Net-(E14D-O)") (class "Default")
      (node (ref "E14") (pin "13") (pinfunction "O_13") (pintype "output"))
      (node (ref "E17") (pin "11") (pinfunction "I_11") (pintype "input"))
      (node (ref "E3") (pin "14") (pinfunction "J_14") (pintype "input"))
      (node (ref "E3") (pin "3") (pinfunction "K_3") (pintype "input"))
    )
    (net (code "83") (name "Net-(E15A-J)") (class "Default")
      (node (ref "E15") (pin "14") (pinfunction "J_14") (pintype "input"))
      (node (ref "E15") (pin "8") (pinfunction "~{Q}_8") (pintype "output"))
      (node (ref "E4") (pin "11") (pinfunction "I0_11") (pintype "input"))
      (node (ref "E4") (pin "3") (pinfunction "I1_3") (pintype "input"))
    )
    (net (code "84") (name "Net-(E15A-K)") (class "Default")
      (node (ref "E15") (pin "3") (pinfunction "K_3") (pintype "input"))
      (node (ref "E15") (pin "9") (pinfunction "Q_9") (pintype "output"))
      (node (ref "E18") (pin "7") (pinfunction "J_7") (pintype "input"))
      (node (ref "TP6") (pin "1") (pinfunction "P_1") (pintype "passive"))
    )
    (net (code "85") (name "Net-(E15B-J)") (class "Default")
      (node (ref "E15") (pin "7") (pinfunction "J_7") (pintype "input"))
      (node (ref "E17") (pin "10") (pinfunction "O_10") (pintype "output"))
    )
    (net (code "86") (name "Net-(E15B-K)") (class "Default")
      (node (ref "E15") (pin "10") (pinfunction "K_10") (pintype "input"))
      (node (ref "E17") (pin "4") (pinfunction "O_4") (pintype "output"))
    )
    (net (code "87") (name "Net-(E17A-I)") (class "Default")
      (node (ref "E17") (pin "1") (pinfunction "I_1") (pintype "input"))
      (node (ref "E3") (pin "8") (pinfunction "~{Q}_8") (pintype "output"))
    )
    (net (code "88") (name "Net-(E17A-O)") (class "Default")
      (node (ref "D1") (pin "A") (pinfunction "A_A") (pintype "passive"))
      (node (ref "E17") (pin "2") (pinfunction "O_2") (pintype "output"))
    )
    (net (code "89") (name "Net-(E17B-I)") (class "Default")
      (node (ref "E17") (pin "3") (pinfunction "I_3") (pintype "input"))
      (node (ref "E4") (pin "10") (pinfunction "O_10") (pintype "output"))
    )
    (net (code "90") (name "Net-(E17C-O)") (class "Default")
      (node (ref "E17") (pin "6") (pinfunction "O_6") (pintype "output"))
      (node (ref "R22") (pin "1") (pinfunction "1_1") (pintype "passive"))
    )
    (net (code "91") (name "Net-(E17D-I)") (class "Default")
      (node (ref "E17") (pin "9") (pinfunction "I_9") (pintype "input"))
      (node (ref "R3") (pin "2") (pinfunction "2_2") (pintype "passive"))
      (node (ref "R4") (pin "1") (pinfunction "1_1") (pintype "passive"))
    )
    (net (code "92") (name "Net-(E17F-I)") (class "Default")
      (node (ref "E17") (pin "13") (pinfunction "I_13") (pintype "input"))
      (node (ref "E18") (pin "8") (pinfunction "~{Q}_8") (pintype "output"))
    )
    (net (code "93") (name "Net-(E17F-O)") (class "Default")
      (node (ref "1.0|2.0") (pin "1") (pinfunction "1_1") (pintype "passive"))
      (node (ref "E17") (pin "12") (pinfunction "O_12") (pintype "output"))
    )
    (net (code "94") (name "Net-(E18A-J)") (class "Default")
      (node (ref "E18") (pin "14") (pinfunction "J_14") (pintype "input"))
      (node (ref "E18") (pin "9") (pinfunction "Q_9") (pintype "output"))
      (node (ref "E4") (pin "8") (pinfunction "I0_8") (pintype "input"))
    )
    (net (code "95") (name "Net-(E18A-K)") (class "Default")
      (node (ref "1.0|2.0") (pin "2") (pinfunction "2_2") (pintype "passive"))
      (node (ref "1.5") (pin "1") (pinfunction "1_1") (pintype "passive"))
      (node (ref "E18") (pin "10") (pinfunction "K_10") (pintype "input"))
      (node (ref "E18") (pin "3") (pinfunction "K_3") (pintype "input"))
    )
    (net (code "96") (name "Net-(E18A-Q)") (class "Default")
      (node (ref "1.5") (pin "2") (pinfunction "2_2") (pintype "passive"))
      (node (ref "1.5|2.0-1.0") (pin "1") (pinfunction "1_1") (pintype "passive"))
      (node (ref "E18") (pin "12") (pinfunction "Q_12") (pintype "output"))
    )
    (net (code "97") (name "Net-(Q1-B)") (class "Default")
      (node (ref "Q1") (pin "2") (pinfunction "B_2") (pintype "passive"))
      (node (ref "R35") (pin "1") (pinfunction "1_1") (pintype "passive"))
      (node (ref "R36") (pin "2") (pinfunction "2_2") (pintype "passive"))
    )
    (net (code "98") (name "Net-(Q2-B)") (class "Default")
      (node (ref "Q2") (pin "2") (pinfunction "B_2") (pintype "passive"))
      (node (ref "R33") (pin "1") (pinfunction "1_1") (pintype "passive"))
      (node (ref "R34") (pin "2") (pinfunction "2_2") (pintype "passive"))
    )
    (net (code "99") (name "Net-(Q3-B)") (class "Default")
      (node (ref "Q3") (pin "2") (pinfunction "B_2") (pintype "passive"))
      (node (ref "R31") (pin "1") (pinfunction "1_1") (pintype "passive"))
      (node (ref "R32") (pin "2") (pinfunction "2_2") (pintype "passive"))
    )
    (net (code "100") (name "Net-(Q4-B)") (class "Default")
      (node (ref "Q4") (pin "2") (pinfunction "B_2") (pintype "passive"))
      (node (ref "R29") (pin "1") (pinfunction "1_1") (pintype "passive"))
      (node (ref "R30") (pin "2") (pinfunction "2_2") (pintype "passive"))
    )
    (net (code "101") (name "Net-(Q5-B)") (class "Default")
      (node (ref "Q5") (pin "2") (pinfunction "B_2") (pintype "passive"))
      (node (ref "R27") (pin "1") (pinfunction "1_1") (pintype "passive"))
      (node (ref "R28") (pin "2") (pinfunction "2_2") (pintype "passive"))
    )
    (net (code "102") (name "Net-(Q6-B)") (class "Default")
      (node (ref "Q6") (pin "2") (pinfunction "B_2") (pintype "passive"))
      (node (ref "R25") (pin "1") (pinfunction "1_1") (pintype "passive"))
      (node (ref "R26") (pin "2") (pinfunction "2_2") (pintype "passive"))
    )
    (net (code "103") (name "Net-(Q7-B)") (class "Default")
      (node (ref "Q7") (pin "2") (pinfunction "B_2") (pintype "passive"))
      (node (ref "R23") (pin "1") (pinfunction "1_1") (pintype "passive"))
      (node (ref "R24") (pin "2") (pinfunction "2_2") (pintype "passive"))
    )
    (net (code "104") (name "Net-(Q8-B)") (class "Default")
      (node (ref "Q8") (pin "2") (pinfunction "B_2") (pintype "passive"))
      (node (ref "R21") (pin "1") (pinfunction "1_1") (pintype "passive"))
      (node (ref "R22") (pin "2") (pinfunction "2_2") (pintype "passive"))
    )
    (net (code "105") (name "Net-(Q9-B)") (class "Default")
      (node (ref "Q9") (pin "2") (pinfunction "B_2") (pintype "passive"))
      (node (ref "R19") (pin "1") (pinfunction "1_1") (pintype "passive"))
      (node (ref "R20") (pin "2") (pinfunction "2_2") (pintype "passive"))
    )
    (net (code "106") (name "Net-(Q10-B)") (class "Default")
      (node (ref "Q10") (pin "2") (pinfunction "B_2") (pintype "passive"))
      (node (ref "R17") (pin "1") (pinfunction "1_1") (pintype "passive"))
      (node (ref "R18") (pin "2") (pinfunction "2_2") (pintype "passive"))
    )
    (net (code "107") (name "Net-(Q11-B)") (class "Default")
      (node (ref "Q11") (pin "2") (pinfunction "B_2") (pintype "passive"))
      (node (ref "R15") (pin "1") (pinfunction "1_1") (pintype "passive"))
      (node (ref "R16") (pin "2") (pinfunction "2_2") (pintype "passive"))
    )
    (net (code "108") (name "Net-(Q12-B)") (class "Default")
      (node (ref "D2") (pin "C") (pinfunction "C_C") (pintype "passive"))
      (node (ref "Q12") (pin "2") (pinfunction "B_2") (pintype "passive"))
      (node (ref "R37") (pin "1") (pinfunction "1_1") (pintype "passive"))
    )
    (net (code "109") (name "Net-(U$2BN-1)") (class "Default")
      (node (ref "R1") (pin "1") (pinfunction "1_1") (pintype "passive"))
      (node (ref "U$2") (pin "BS2") (pinfunction "1_BS2") (pintype "bidirectional"))
    )
    (net (code "110") (name "Net-(U$2BP-1)") (class "Default")
      (node (ref "R11") (pin "1") (pinfunction "1_1") (pintype "passive"))
      (node (ref "U$2") (pin "BT2") (pinfunction "1_BT2") (pintype "bidirectional"))
    )
    (net (code "111") (name "Net-(U$2BT-1)") (class "Default")
      (node (ref "R3") (pin "1") (pinfunction "1_1") (pintype "passive"))
      (node (ref "U$2") (pin "BV2") (pinfunction "1_BV2") (pintype "bidirectional"))
    )
    (net (code "112") (name "Net-(U$2H-1)") (class "Default")
      (node (ref "R5") (pin "1") (pinfunction "1_1") (pintype "passive"))
      (node (ref "U$2") (pin "AD2") (pinfunction "1_AD2") (pintype "bidirectional"))
    )
    (net (code "113") (name "Net-(U$2L-1)") (class "Default")
      (node (ref "R9") (pin "2") (pinfunction "2_2") (pintype "passive"))
      (node (ref "U$2") (pin "AF2") (pinfunction "1_AF2") (pintype "bidirectional"))
    )
    (net (code "114") (name "VCC") (class "Default")
      (node (ref "C1") (pin "1") (pinfunction "1_1") (pintype "passive"))
      (node (ref "C10") (pin "1") (pinfunction "1_1") (pintype "passive"))
      (node (ref "C11") (pin "1") (pinfunction "1_1") (pintype "passive"))
      (node (ref "C12") (pin "1") (pinfunction "1_1") (pintype "passive"))
      (node (ref "C13") (pin "1") (pinfunction "1_1") (pintype "passive"))
      (node (ref "C14") (pin "1") (pinfunction "1_1") (pintype "passive"))
      (node (ref "C15") (pin "1") (pinfunction "1_1") (pintype "passive"))
      (node (ref "C17") (pin "1") (pinfunction "1_1") (pintype "passive"))
      (node (ref "C18") (pin "1") (pinfunction "1_1") (pintype "passive"))
      (node (ref "C2") (pin "1") (pinfunction "1_1") (pintype "passive"))
      (node (ref "C3") (pin "1") (pinfunction "1_1") (pintype "passive"))
      (node (ref "C4") (pin "1") (pinfunction "1_1") (pintype "passive"))
      (node (ref "C5") (pin "1") (pinfunction "1_1") (pintype "passive"))
      (node (ref "C6") (pin "1") (pinfunction "1_1") (pintype "passive"))
      (node (ref "C7") (pin "1") (pinfunction "1_1") (pintype "passive"))
      (node (ref "C8") (pin "1") (pinfunction "1_1") (pintype "passive"))
      (node (ref "C9") (pin "1") (pinfunction "1_1") (pintype "passive"))
      (node (ref "E3") (pin "10") (pinfunction "K_10") (pintype "input"))
      (node (ref "E5") (pin "10") (pinfunction "K_10") (pintype "input"))
      (node (ref "E5") (pin "3") (pinfunction "K_3") (pintype "input"))
      (node (ref "R10") (pin "2") (pinfunction "2_2") (pintype "passive"))
      (node (ref "R12") (pin "2") (pinfunction "2_2") (pintype "passive"))
      (node (ref "R14") (pin "2") (pinfunction "2_2") (pintype "passive"))
      (node (ref "R2") (pin "2") (pinfunction "2_2") (pintype "passive"))
      (node (ref "R4") (pin "2") (pinfunction "2_2") (pintype "passive"))
      (node (ref "R6") (pin "2") (pinfunction "2_2") (pintype "passive"))
      (node (ref "R7") (pin "2") (pinfunction "2_2") (pintype "passive"))
      (node (ref "R8") (pin "2") (pinfunction "2_2") (pintype "passive"))
      (node (ref "U$2") (pin "AJ2") (pinfunction "1_AJ2") (pintype "bidirectional"))
    )
    (net (code "115") (name "unconnected-(E1B-O-Pad6)") (class "Default")
      (node (ref "E1") (pin "6") (pinfunction "O_6") (pintype "output"))
    )
    (net (code "116") (name "unconnected-(E1C-O-Pad8)") (class "Default")
      (node (ref "E1") (pin "8") (pinfunction "O_8") (pintype "output"))
    )
    (net (code "117") (name "unconnected-(E1D-O-Pad11)") (class "Default")
      (node (ref "E1") (pin "11") (pinfunction "O_11") (pintype "output"))
    )
    (net (code "118") (name "unconnected-(E2E-O-Pad10)") (class "Default")
      (node (ref "E2") (pin "10") (pinfunction "O_10") (pintype "output"))
    )
    (net (code "119") (name "unconnected-(E3A-~{Q}-Pad13)") (class "Default")
      (node (ref "E3") (pin "13") (pinfunction "~{Q}_13") (pintype "output"))
    )
    (net (code "120") (name "unconnected-(E3B-Q-Pad9)") (class "Default")
      (node (ref "E3") (pin "9") (pinfunction "Q_9") (pintype "output"))
    )
    (net (code "121") (name "unconnected-(E5A-~{Q}-Pad13)") (class "Default")
      (node (ref "E5") (pin "13") (pinfunction "~{Q}_13") (pintype "output"))
    )
    (net (code "122") (name "unconnected-(E12E-O-Pad10)") (class "Default")
      (node (ref "E12") (pin "10") (pinfunction "O_10") (pintype "output"))
    )
    (net (code "123") (name "unconnected-(E15A-Q-Pad12)") (class "Default")
      (node (ref "E15") (pin "12") (pinfunction "Q_12") (pintype "output"))
    )
    (net (code "124") (name "unconnected-(E18A-~{Q}-Pad13)") (class "Default")
      (node (ref "E18") (pin "13") (pinfunction "~{Q}_13") (pintype "output"))
    )
  )
)
